# untitled.net
KiCad netlist of a schematic drawn in EAGLE
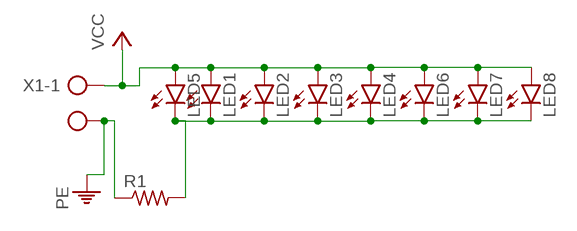
[diagram p0: schematic, sheet 1]

(export (version "E")
  (design (tool "Eeschema 10.0.6"))
  (components
    (comp (ref "LED1")
      (value "LED5MM")
      (footprint "eagle-import:LED5MM")
      (libsource (lib "eagle-import") (part "LED5MM"))
    )
    (comp (ref "LED2")
      (value "LED5MM")
      (footprint "eagle-import:LED5MM")
      (libsource (lib "eagle-import") (part "LED5MM"))
    )
    (comp (ref "LED3")
      (value "LED5MM")
      (footprint "eagle-import:LED5MM")
      (libsource (lib "eagle-import") (part "LED5MM"))
    )
    (comp (ref "LED4")
      (value "LED5MM")
      (footprint "eagle-import:LED5MM")
      (libsource (lib "eagle-import") (part "LED5MM"))
    )
    (comp (ref "LED5")
      (value "LED5MM")
      (footprint "eagle-import:LED5MM")
      (libsource (lib "eagle-import") (part "LED5MM"))
    )
    (comp (ref "LED6")
      (value "LED5MM")
      (footprint "eagle-import:LED5MM")
      (libsource (lib "eagle-import") (part "LED5MM"))
    )
    (comp (ref "LED7")
      (value "LED5MM")
      (footprint "eagle-import:LED5MM")
      (libsource (lib "eagle-import") (part "LED5MM"))
    )
    (comp (ref "LED8")
      (value "LED5MM")
      (footprint "eagle-import:LED5MM")
      (libsource (lib "eagle-import") (part "LED5MM"))
    )
    (comp (ref "R1")
      (value "R-US_0204/7")
      (footprint "eagle-import:0204_7")
      (libsource (lib "eagle-import") (part "R-US_0204/7"))
    )
    (comp (ref "X1")
      (value "AK500/2-H")
      (footprint "eagle-import:AK500_2-H")
      (libsource (lib "eagle-import") (part "AK500/2-H"))
    )
  )
  (nets
    (net (code "1") (name "Net-(LED1-C)") (class "Default")
      (node (ref "LED1") (pin "K") (pinfunction "C_K") (pintype "passive"))
      (node (ref "LED2") (pin "K") (pinfunction "C_K") (pintype "passive"))
      (node (ref "LED3") (pin "K") (pinfunction "C_K") (pintype "passive"))
      (node (ref "LED4") (pin "K") (pinfunction "C_K") (pintype "passive"))
      (node (ref "LED5") (pin "K") (pinfunction "C_K") (pintype "passive"))
      (node (ref "LED6") (pin "K") (pinfunction "C_K") (pintype "passive"))
      (node (ref "LED7") (pin "K") (pinfunction "C_K") (pintype "passive"))
      (node (ref "LED8") (pin "K") (pinfunction "C_K") (pintype "passive"))
      (node (ref "R1") (pin "2") (pinfunction "2_2") (pintype "passive"))
    )
    (net (code "2") (name "PE") (class "Default")
      (node (ref "R1") (pin "1") (pinfunction "1_1") (pintype "passive"))
      (node (ref "X1") (pin "2") (pinfunction "KL_2") (pintype "passive"))
    )
    (net (code "3") (name "VCC") (class "Default")
      (node (ref "LED1") (pin "A") (pinfunction "A_A") (pintype "passive"))
      (node (ref "LED2") (pin "A") (pinfunction "A_A") (pintype "passive"))
      (node (ref "LED3") (pin "A") (pinfunction "A_A") (pintype "passive"))
      (node (ref "LED4") (pin "A") (pinfunction "A_A") (pintype "passive"))
      (node (ref "LED5") (pin "A") (pinfunction "A_A") (pintype "passive"))
      (node (ref "LED6") (pin "A") (pinfunction "A_A") (pintype "passive"))
      (node (ref "LED7") (pin "A") (pinfunction "A_A") (pintype "passive"))
      (node (ref "LED8") (pin "A") (pinfunction "A_A") (pintype "passive"))
      (node (ref "X1") (pin "1") (pinfunction "KL_1") (pintype "passive"))
    )
  )
)
